# GasSensorCentral_v1_3.net
KiCad netlist of a schematic drawn in EAGLE
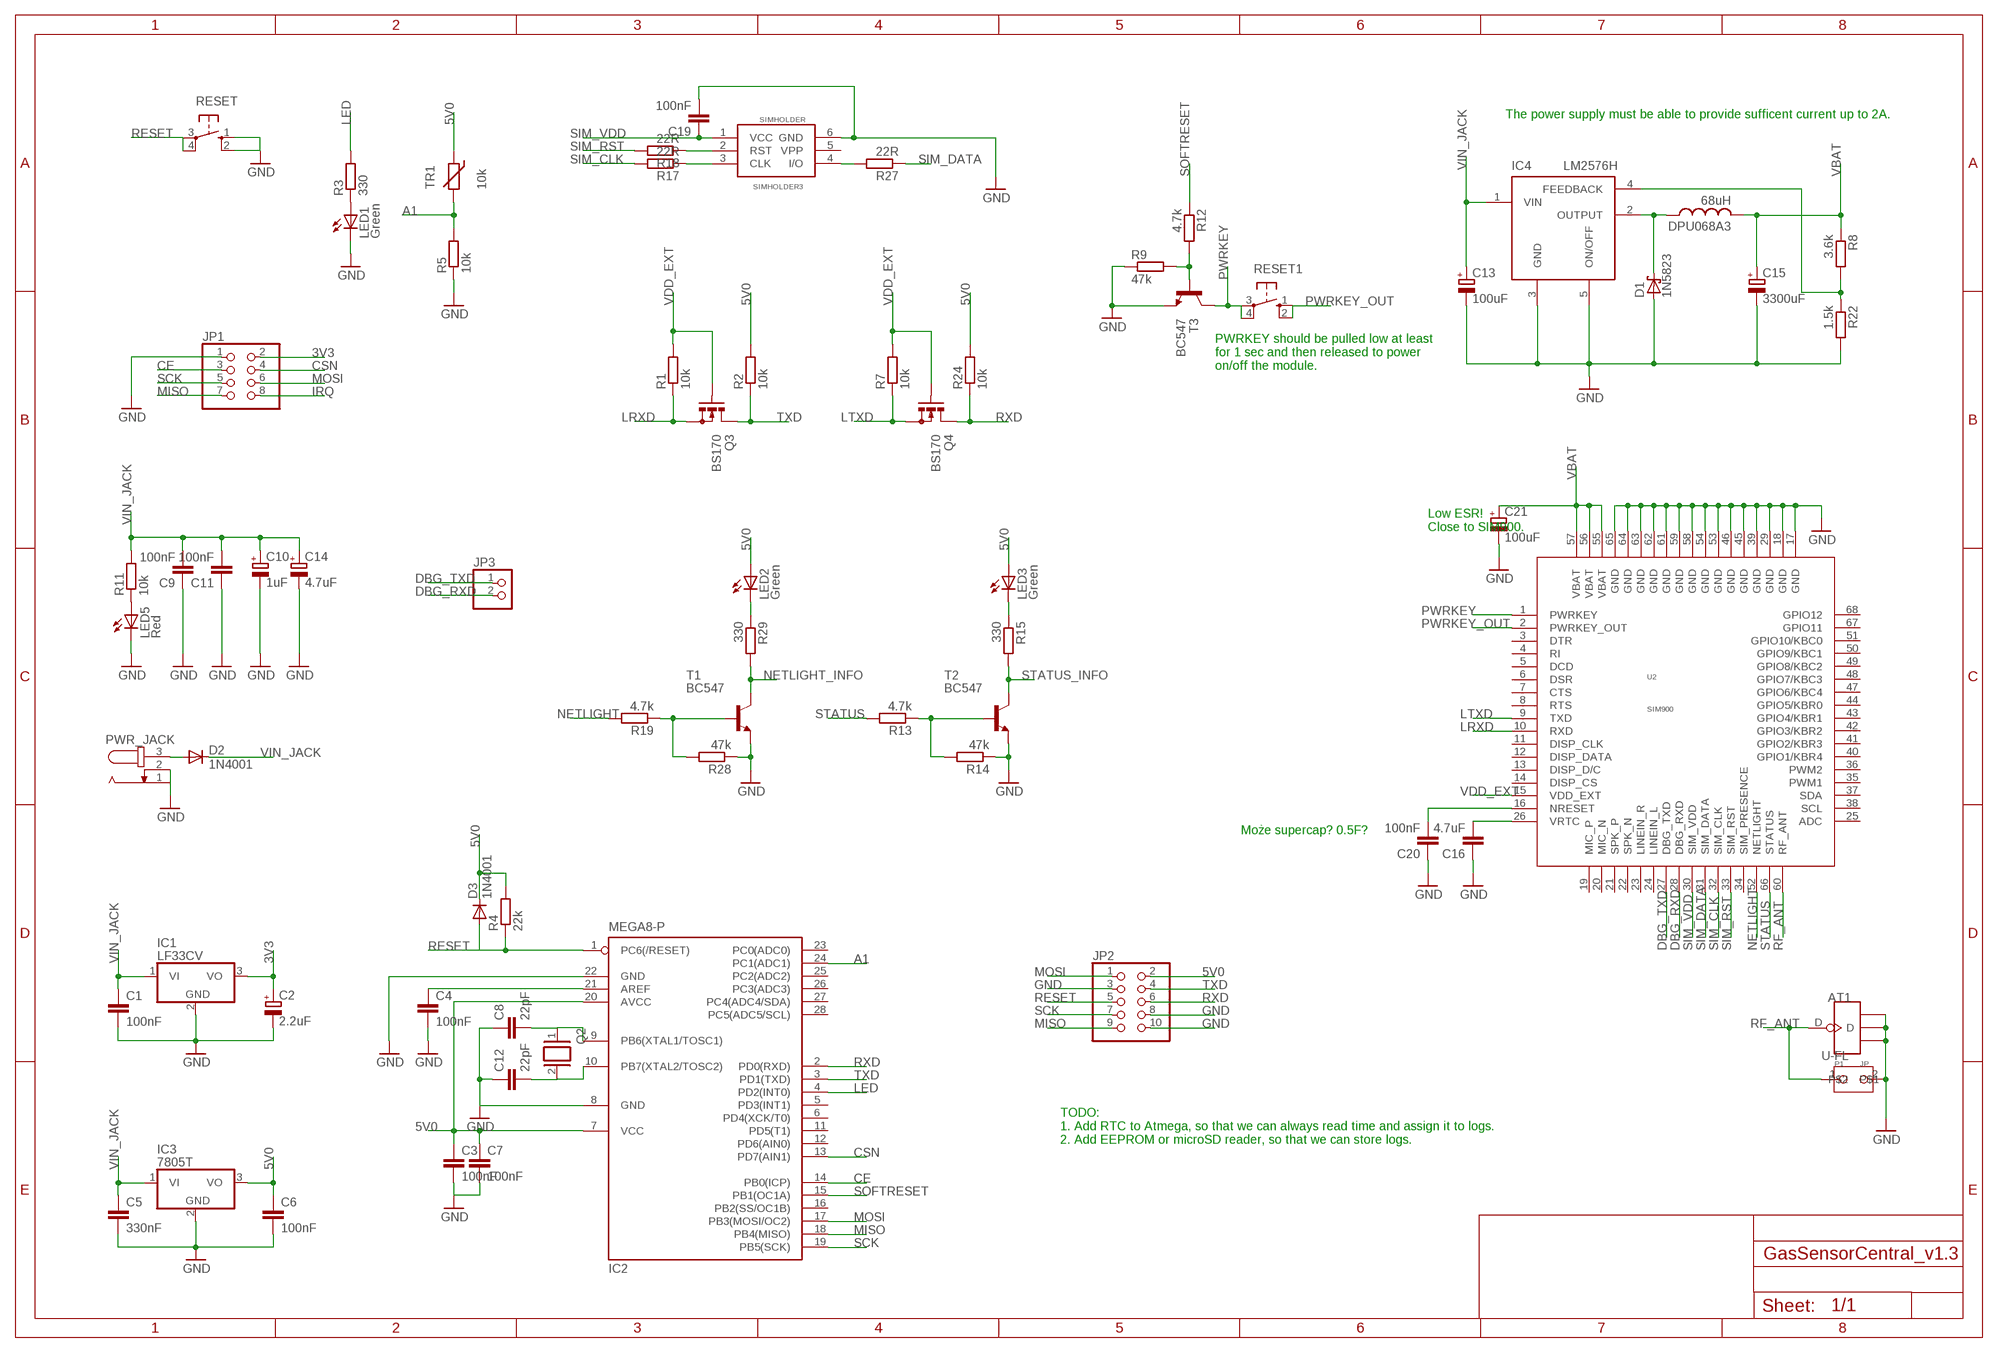
[diagram p0: schematic, sheet 1]

(export (version "E")
  (design (tool "Eeschema 10.0.6"))
  (components
    (comp (ref "AT1")
      (value "U-FL")
      (footprint "eagle-import:4P-U-FL")
      (libsource (lib "eagle-import") (part "ANTENNA-U-FL"))
    )
    (comp (ref "C1")
      (value "100nF")
      (footprint "eagle-import:C025-025X050")
      (libsource (lib "eagle-import") (part "C-EU025-025X050"))
    )
    (comp (ref "C2")
      (value "2.2uF")
      (footprint "eagle-import:E2,5-5")
      (libsource (lib "eagle-import") (part "CPOL-EUE2.5-5"))
    )
    (comp (ref "C3")
      (value "100nF")
      (footprint "eagle-import:C025-025X050")
      (libsource (lib "eagle-import") (part "C-EU025-025X050"))
    )
    (comp (ref "C4")
      (value "100nF")
      (footprint "eagle-import:C025-025X050")
      (libsource (lib "eagle-import") (part "C-EU025-025X050"))
    )
    (comp (ref "C5")
      (value "330nF")
      (footprint "eagle-import:C025-025X050")
      (libsource (lib "eagle-import") (part "C-EU025-025X050"))
    )
    (comp (ref "C6")
      (value "100nF")
      (footprint "eagle-import:C025-025X050")
      (libsource (lib "eagle-import") (part "C-EU025-025X050"))
    )
    (comp (ref "C7")
      (value "100nF")
      (footprint "eagle-import:C025-025X050")
      (libsource (lib "eagle-import") (part "C-EU025-025X050"))
    )
    (comp (ref "C8")
      (value "22pF")
      (footprint "eagle-import:C025-025X050")
      (libsource (lib "eagle-import") (part "C-EU025-025X050"))
    )
    (comp (ref "C9")
      (value "100nF")
      (footprint "eagle-import:C025-025X050")
      (libsource (lib "eagle-import") (part "C-EU025-025X050"))
    )
    (comp (ref "C10")
      (value "1uF")
      (footprint "eagle-import:E2,5-5")
      (libsource (lib "eagle-import") (part "CPOL-EUE2.5-5"))
    )
    (comp (ref "C11")
      (value "100nF")
      (footprint "eagle-import:C025-025X050")
      (libsource (lib "eagle-import") (part "C-EU025-025X050"))
    )
    (comp (ref "C12")
      (value "22pF")
      (footprint "eagle-import:C025-025X050")
      (libsource (lib "eagle-import") (part "C-EU025-025X050"))
    )
    (comp (ref "C13")
      (value "100uF")
      (footprint "eagle-import:E2,5-5")
      (libsource (lib "eagle-import") (part "CPOL-EUE2.5-5"))
    )
    (comp (ref "C14")
      (value "4.7uF")
      (footprint "eagle-import:E2,5-5")
      (libsource (lib "eagle-import") (part "CPOL-EUE2.5-5"))
    )
    (comp (ref "C15")
      (value "3300uF")
      (footprint "eagle-import:E3,5-10")
      (libsource (lib "eagle-import") (part "CPOL-EUE3.5-10"))
    )
    (comp (ref "C16")
      (value "4.7uF")
      (footprint "eagle-import:C025-025X050")
      (libsource (lib "eagle-import") (part "C-EU025-025X050"))
    )
    (comp (ref "C19")
      (value "100nF")
      (footprint "eagle-import:C025-025X050")
      (libsource (lib "eagle-import") (part "C-EU025-025X050"))
    )
    (comp (ref "C20")
      (value "100nF")
      (footprint "eagle-import:C025-025X050")
      (libsource (lib "eagle-import") (part "C-EU025-025X050"))
    )
    (comp (ref "C21")
      (value "100uF")
      (footprint "eagle-import:E2,5-5")
      (libsource (lib "eagle-import") (part "CPOL-EUE2.5-5"))
    )
    (comp (ref "D1")
      (value "1N5823")
      (footprint "eagle-import:DO41-7.6")
      (libsource (lib "eagle-import") (part "1N5817-B"))
    )
    (comp (ref "D2")
      (value "1N4001")
      (footprint "eagle-import:DO41-10")
      (libsource (lib "eagle-import") (part "1N4004"))
    )
    (comp (ref "D3")
      (value "1N4001")
      (footprint "eagle-import:DO41-10")
      (libsource (lib "eagle-import") (part "1N4004"))
    )
    (comp (ref "DPU068A3")
      (value "68uH")
      (footprint "eagle-import:TJ3-U1")
      (libsource (lib "eagle-import") (part "L-USTJ3-U1"))
    )
    (comp (ref "IC1")
      (value "LF33CV")
      (footprint "eagle-import:TO220H")
      (libsource (lib "eagle-import") (part "78T05"))
    )
    (comp (ref "IC2")
      (value "MEGA8-P")
      (footprint "eagle-import:DIL28-3")
      (libsource (lib "eagle-import") (part "MEGA8-P"))
    )
    (comp (ref "IC3")
      (value "7805T")
      (footprint "eagle-import:TO220H")
      (libsource (lib "eagle-import") (part "78T05"))
    )
    (comp (ref "IC4")
      (value "LM2576H")
      (footprint "eagle-import:TO220-52")
      (libsource (lib "eagle-import") (part "LM2576H"))
    )
    (comp (ref "JP1")
      (value "PINHD-2X4")
      (footprint "eagle-import:2X04")
      (libsource (lib "eagle-import") (part "PINHD-2X4"))
    )
    (comp (ref "JP2")
      (value "PINHD-2X5")
      (footprint "eagle-import:2X05")
      (libsource (lib "eagle-import") (part "PINHD-2X5"))
    )
    (comp (ref "JP3")
      (value "PINHD-1X2")
      (footprint "eagle-import:1X02")
      (libsource (lib "eagle-import") (part "PINHD-1X2"))
    )
    (comp (ref "LED1")
      (value "Green")
      (footprint "eagle-import:LED3MM")
      (libsource (lib "eagle-import") (part "LED3MM"))
    )
    (comp (ref "LED2")
      (value "Green")
      (footprint "eagle-import:LED3MM")
      (libsource (lib "eagle-import") (part "LED3MM"))
    )
    (comp (ref "LED3")
      (value "Green")
      (footprint "eagle-import:LED3MM")
      (libsource (lib "eagle-import") (part "LED3MM"))
    )
    (comp (ref "LED5")
      (value "Red")
      (footprint "eagle-import:LED3MM")
      (libsource (lib "eagle-import") (part "LED3MM"))
    )
    (comp (ref "P1") (value "JP") (footprint "eagle-import:JP") (libsource (lib "eagle-import") (part "JP")))
    (comp (ref "PWR_JACK")
      (value "JACK-PLUG0")
      (footprint "eagle-import:SPC4077")
      (libsource (lib "eagle-import") (part "JACK-PLUG0"))
    )
    (comp (ref "Q2")
      (value "XTAL/S")
      (footprint "eagle-import:QS")
      (libsource (lib "eagle-import") (part "XTAL/S"))
    )
    (comp (ref "Q3")
      (value "BS170")
      (footprint "eagle-import:SOT54E")
      (libsource (lib "eagle-import") (part "BS170"))
    )
    (comp (ref "Q4")
      (value "BS170")
      (footprint "eagle-import:SOT54E")
      (libsource (lib "eagle-import") (part "BS170"))
    )
    (comp (ref "R1")
      (value "10k")
      (footprint "eagle-import:0207_10")
      (libsource (lib "eagle-import") (part "R-EU_0207/10"))
    )
    (comp (ref "R2")
      (value "10k")
      (footprint "eagle-import:0207_10")
      (libsource (lib "eagle-import") (part "R-EU_0207/10"))
    )
    (comp (ref "R3")
      (value "330")
      (footprint "eagle-import:0207_10")
      (libsource (lib "eagle-import") (part "R-EU_0207/10"))
    )
    (comp (ref "R4")
      (value "22k")
      (footprint "eagle-import:0207_10")
      (libsource (lib "eagle-import") (part "R-EU_0207/10"))
    )
    (comp (ref "R5")
      (value "10k")
      (footprint "eagle-import:0207_10")
      (libsource (lib "eagle-import") (part "R-EU_0207/10"))
    )
    (comp (ref "R7")
      (value "10k")
      (footprint "eagle-import:0207_10")
      (libsource (lib "eagle-import") (part "R-EU_0207/10"))
    )
    (comp (ref "R8")
      (value "3.6k")
      (footprint "eagle-import:0207_10")
      (libsource (lib "eagle-import") (part "R-EU_0207/10"))
    )
    (comp (ref "R9")
      (value "47k")
      (footprint "eagle-import:0207_10")
      (libsource (lib "eagle-import") (part "R-EU_0207/10"))
    )
    (comp (ref "R11")
      (value "10k")
      (footprint "eagle-import:0207_10")
      (libsource (lib "eagle-import") (part "R-EU_0207/10"))
    )
    (comp (ref "R12")
      (value "4.7k")
      (footprint "eagle-import:0207_10")
      (libsource (lib "eagle-import") (part "R-EU_0207/10"))
    )
    (comp (ref "R13")
      (value "4.7k")
      (footprint "eagle-import:0207_10")
      (libsource (lib "eagle-import") (part "R-EU_0207/10"))
    )
    (comp (ref "R14")
      (value "47k")
      (footprint "eagle-import:0207_10")
      (libsource (lib "eagle-import") (part "R-EU_0207/10"))
    )
    (comp (ref "R15")
      (value "330")
      (footprint "eagle-import:0207_10")
      (libsource (lib "eagle-import") (part "R-EU_0207/10"))
    )
    (comp (ref "R17")
      (value "22R")
      (footprint "eagle-import:0207_10")
      (libsource (lib "eagle-import") (part "R-EU_0207/10"))
    )
    (comp (ref "R18")
      (value "22R")
      (footprint "eagle-import:0207_10")
      (libsource (lib "eagle-import") (part "R-EU_0207/10"))
    )
    (comp (ref "R19")
      (value "4.7k")
      (footprint "eagle-import:0207_10")
      (libsource (lib "eagle-import") (part "R-EU_0207/10"))
    )
    (comp (ref "R22")
      (value "1.5k")
      (footprint "eagle-import:0207_10")
      (libsource (lib "eagle-import") (part "R-EU_0207/10"))
    )
    (comp (ref "R24")
      (value "10k")
      (footprint "eagle-import:0207_10")
      (libsource (lib "eagle-import") (part "R-EU_0207/10"))
    )
    (comp (ref "R27")
      (value "22R")
      (footprint "eagle-import:0207_10")
      (libsource (lib "eagle-import") (part "R-EU_0207/10"))
    )
    (comp (ref "R28")
      (value "47k")
      (footprint "eagle-import:0207_10")
      (libsource (lib "eagle-import") (part "R-EU_0207/10"))
    )
    (comp (ref "R29")
      (value "330")
      (footprint "eagle-import:0207_10")
      (libsource (lib "eagle-import") (part "R-EU_0207/10"))
    )
    (comp (ref "RESET")
      (value "10-XX")
      (footprint "eagle-import:B3F-10XX")
      (fields (field (name "MPN") "B3F-1000"))
      (libsource (lib "eagle-import") (part "10-XX"))
    )
    (comp (ref "RESET1")
      (value "10-XX")
      (footprint "eagle-import:B3F-10XX")
      (fields (field (name "MPN") "B3F-1000"))
      (libsource (lib "eagle-import") (part "10-XX"))
    )
    (comp (ref "SIMHOLDER")
      (value "SIMHOLDER3")
      (footprint "eagle-import:SIMHOLDER3")
      (libsource (lib "eagle-import") (part "SIMHOLDER3"))
    )
    (comp (ref "T1")
      (value "BC547")
      (footprint "eagle-import:TO92")
      (libsource (lib "eagle-import") (part "BC547"))
    )
    (comp (ref "T2")
      (value "BC547")
      (footprint "eagle-import:TO92")
      (libsource (lib "eagle-import") (part "BC547"))
    )
    (comp (ref "T3")
      (value "BC547")
      (footprint "eagle-import:TO92")
      (libsource (lib "eagle-import") (part "BC547"))
    )
    (comp (ref "TR1")
      (value "10k")
      (footprint "eagle-import:RS-2,5")
      (libsource (lib "eagle-import") (part "THERMISTOR_R-2,5"))
    )
    (comp (ref "U2")
      (value "SIM900")
      (footprint "eagle-import:SIM900")
      (libsource (lib "eagle-import") (part "SIM900"))
    )
  )
  (nets
    (net (code "1") (name "/3V3") (class "Default")
      (node (ref "C2") (pin "+") (pinfunction "+_+") (pintype "passive"))
      (node (ref "IC1") (pin "3") (pinfunction "VO_3") (pintype "passive"))
      (node (ref "JP1") (pin "2") (pinfunction "2_2") (pintype "passive"))
    )
    (net (code "2") (name "/5V0") (class "Default")
      (node (ref "C3") (pin "1") (pinfunction "1_1") (pintype "passive"))
      (node (ref "C6") (pin "1") (pinfunction "1_1") (pintype "passive"))
      (node (ref "C7") (pin "1") (pinfunction "1_1") (pintype "passive"))
      (node (ref "D3") (pin "C") (pinfunction "C_C") (pintype "passive"))
      (node (ref "IC2") (pin "20") (pinfunction "AVCC_20") (pintype "power_in"))
      (node (ref "IC2") (pin "7") (pinfunction "VCC_7") (pintype "power_in"))
      (node (ref "IC3") (pin "3") (pinfunction "VO_3") (pintype "passive"))
      (node (ref "JP2") (pin "2") (pinfunction "2_2") (pintype "passive"))
      (node (ref "LED2") (pin "A") (pinfunction "A_A") (pintype "passive"))
      (node (ref "LED3") (pin "A") (pinfunction "A_A") (pintype "passive"))
      (node (ref "R2") (pin "2") (pinfunction "2_2") (pintype "passive"))
      (node (ref "R24") (pin "2") (pinfunction "2_2") (pintype "passive"))
      (node (ref "R4") (pin "2") (pinfunction "2_2") (pintype "passive"))
      (node (ref "TR1") (pin "1") (pinfunction "1_1") (pintype "passive"))
    )
    (net (code "3") (name "/A1") (class "Default")
      (node (ref "IC2") (pin "24") (pinfunction "PC1(ADC1)_24") (pintype "bidirectional"))
      (node (ref "R5") (pin "2") (pinfunction "2_2") (pintype "passive"))
      (node (ref "TR1") (pin "2") (pinfunction "2_2") (pintype "passive"))
    )
    (net (code "4") (name "/CE") (class "Default")
      (node (ref "IC2") (pin "14") (pinfunction "PB0(ICP)_14") (pintype "bidirectional"))
      (node (ref "JP1") (pin "3") (pinfunction "3_3") (pintype "passive"))
    )
    (net (code "5") (name "/CSN") (class "Default")
      (node (ref "IC2") (pin "13") (pinfunction "PD7(AIN1)_13") (pintype "bidirectional"))
      (node (ref "JP1") (pin "4") (pinfunction "4_4") (pintype "passive"))
    )
    (net (code "6") (name "/DBG_RXD") (class "Default")
      (node (ref "JP3") (pin "2") (pinfunction "2_2") (pintype "passive"))
      (node (ref "U2") (pin "28") (pinfunction "DBG_RXD_28") (pintype "input"))
    )
    (net (code "7") (name "/DBG_TXD") (class "Default")
      (node (ref "JP3") (pin "1") (pinfunction "1_1") (pintype "passive"))
      (node (ref "U2") (pin "27") (pinfunction "DBG_TXD_27") (pintype "output"))
    )
    (net (code "8") (name "/IRQ") (class "Default")
      (node (ref "JP1") (pin "8") (pinfunction "8_8") (pintype "passive"))
    )
    (net (code "9") (name "/LED") (class "Default")
      (node (ref "IC2") (pin "4") (pinfunction "PD2(INT0)_4") (pintype "bidirectional"))
      (node (ref "R3") (pin "2") (pinfunction "2_2") (pintype "passive"))
    )
    (net (code "10") (name "/LRXD") (class "Default")
      (node (ref "Q3") (pin "S") (pinfunction "S_S") (pintype "passive"))
      (node (ref "R1") (pin "1") (pinfunction "1_1") (pintype "passive"))
      (node (ref "U2") (pin "10") (pinfunction "RXD_10") (pintype "input"))
    )
    (net (code "11") (name "/LTXD") (class "Default")
      (node (ref "Q4") (pin "S") (pinfunction "S_S") (pintype "passive"))
      (node (ref "R7") (pin "1") (pinfunction "1_1") (pintype "passive"))
      (node (ref "U2") (pin "9") (pinfunction "TXD_9") (pintype "output"))
    )
    (net (code "12") (name "/MISO") (class "Default")
      (node (ref "IC2") (pin "18") (pinfunction "PB4(MISO)_18") (pintype "bidirectional"))
      (node (ref "JP1") (pin "7") (pinfunction "7_7") (pintype "passive"))
      (node (ref "JP2") (pin "9") (pinfunction "9_9") (pintype "passive"))
    )
    (net (code "13") (name "/MOSI") (class "Default")
      (node (ref "IC2") (pin "17") (pinfunction "PB3(MOSI/OC2)_17") (pintype "bidirectional"))
      (node (ref "JP1") (pin "6") (pinfunction "6_6") (pintype "passive"))
      (node (ref "JP2") (pin "1") (pinfunction "1_1") (pintype "passive"))
    )
    (net (code "14") (name "/NETLIGHT") (class "Default")
      (node (ref "R19") (pin "2") (pinfunction "2_2") (pintype "passive"))
      (node (ref "U2") (pin "52") (pinfunction "NETLIGHT_52") (pintype "output"))
    )
    (net (code "15") (name "/NETLIGHT_INFO") (class "Default")
      (node (ref "R29") (pin "2") (pinfunction "2_2") (pintype "passive"))
      (node (ref "T1") (pin "3") (pinfunction "C_3") (pintype "passive"))
    )
    (net (code "16") (name "/PWRKEY") (class "Default")
      (node (ref "RESET1") (pin "3") (pinfunction "P_3") (pintype "passive"))
      (node (ref "RESET1") (pin "4") (pinfunction "P1_4") (pintype "passive"))
      (node (ref "T3") (pin "3") (pinfunction "C_3") (pintype "passive"))
      (node (ref "U2") (pin "1") (pinfunction "PWRKEY_1") (pintype "input"))
    )
    (net (code "17") (name "/PWRKEY_OUT") (class "Default")
      (node (ref "RESET1") (pin "1") (pinfunction "S_1") (pintype "passive"))
      (node (ref "RESET1") (pin "2") (pinfunction "S1_2") (pintype "passive"))
      (node (ref "U2") (pin "2") (pinfunction "PWRKEY_OUT_2") (pintype "output"))
    )
    (net (code "18") (name "/RESET") (class "Default")
      (node (ref "D3") (pin "A") (pinfunction "A_A") (pintype "passive"))
      (node (ref "IC2") (pin "1") (pinfunction "PC6(/RESET)_1") (pintype "bidirectional"))
      (node (ref "JP2") (pin "5") (pinfunction "5_5") (pintype "passive"))
      (node (ref "R4") (pin "1") (pinfunction "1_1") (pintype "passive"))
      (node (ref "RESET") (pin "3") (pinfunction "P_3") (pintype "passive"))
      (node (ref "RESET") (pin "4") (pinfunction "P1_4") (pintype "passive"))
    )
    (net (code "19") (name "/RF_ANT") (class "Default")
      (node (ref "AT1") (pin "D") (pinfunction "D_D") (pintype "bidirectional"))
      (node (ref "P1") (pin "1") (pinfunction "P$1_1") (pintype "bidirectional"))
      (node (ref "U2") (pin "60") (pinfunction "RF_ANT_60") (pintype "bidirectional"))
    )
    (net (code "20") (name "/RXD") (class "Default")
      (node (ref "IC2") (pin "2") (pinfunction "PD0(RXD)_2") (pintype "bidirectional"))
      (node (ref "JP2") (pin "6") (pinfunction "6_6") (pintype "passive"))
      (node (ref "Q4") (pin "D") (pinfunction "D_D") (pintype "passive"))
      (node (ref "R24") (pin "1") (pinfunction "1_1") (pintype "passive"))
    )
    (net (code "21") (name "/SCK") (class "Default")
      (node (ref "IC2") (pin "19") (pinfunction "PB5(SCK)_19") (pintype "bidirectional"))
      (node (ref "JP1") (pin "5") (pinfunction "5_5") (pintype "passive"))
      (node (ref "JP2") (pin "7") (pinfunction "7_7") (pintype "passive"))
    )
    (net (code "22") (name "/SIM_CLK") (class "Default")
      (node (ref "R17") (pin "2") (pinfunction "2_2") (pintype "passive"))
      (node (ref "U2") (pin "32") (pinfunction "SIM_CLK_32") (pintype "output"))
    )
    (net (code "23") (name "/SIM_DATA") (class "Default")
      (node (ref "R27") (pin "1") (pinfunction "1_1") (pintype "passive"))
      (node (ref "U2") (pin "31") (pinfunction "SIM_DATA_31") (pintype "bidirectional"))
    )
    (net (code "24") (name "/SIM_RST") (class "Default")
      (node (ref "R18") (pin "2") (pinfunction "2_2") (pintype "passive"))
      (node (ref "U2") (pin "33") (pinfunction "SIM_RST_33") (pintype "output"))
    )
    (net (code "25") (name "/SIM_VDD") (class "Default")
      (node (ref "C19") (pin "1") (pinfunction "1_1") (pintype "passive"))
      (node (ref "SIMHOLDER") (pin "1") (pinfunction "VCC_1") (pintype "bidirectional"))
      (node (ref "U2") (pin "30") (pinfunction "SIM_VDD_30") (pintype "output"))
    )
    (net (code "26") (name "/SOFTRESET") (class "Default")
      (node (ref "IC2") (pin "15") (pinfunction "PB1(OC1A)_15") (pintype "bidirectional"))
      (node (ref "R12") (pin "1") (pinfunction "1_1") (pintype "passive"))
    )
    (net (code "27") (name "/STATUS") (class "Default")
      (node (ref "R13") (pin "2") (pinfunction "2_2") (pintype "passive"))
      (node (ref "U2") (pin "66") (pinfunction "STATUS_66") (pintype "output"))
    )
    (net (code "28") (name "/STATUS_INFO") (class "Default")
      (node (ref "R15") (pin "2") (pinfunction "2_2") (pintype "passive"))
      (node (ref "T2") (pin "3") (pinfunction "C_3") (pintype "passive"))
    )
    (net (code "29") (name "/TXD") (class "Default")
      (node (ref "IC2") (pin "3") (pinfunction "PD1(TXD)_3") (pintype "bidirectional"))
      (node (ref "JP2") (pin "4") (pinfunction "4_4") (pintype "passive"))
      (node (ref "Q3") (pin "D") (pinfunction "D_D") (pintype "passive"))
      (node (ref "R2") (pin "1") (pinfunction "1_1") (pintype "passive"))
    )
    (net (code "30") (name "/VBAT") (class "Default")
      (node (ref "C15") (pin "+") (pinfunction "+_+") (pintype "passive"))
      (node (ref "C21") (pin "+") (pinfunction "+_+") (pintype "passive"))
      (node (ref "DPU068A3") (pin "2") (pinfunction "2_2") (pintype "passive"))
      (node (ref "R8") (pin "1") (pinfunction "1_1") (pintype "passive"))
      (node (ref "U2") (pin "55") (pinfunction "VBAT_55") (pintype "power_in"))
      (node (ref "U2") (pin "56") (pinfunction "VBAT_56") (pintype "power_in"))
      (node (ref "U2") (pin "57") (pinfunction "VBAT_57") (pintype "power_in"))
    )
    (net (code "31") (name "/VDD_EXT") (class "Default")
      (node (ref "Q3") (pin "G") (pinfunction "G_G") (pintype "passive"))
      (node (ref "Q4") (pin "G") (pinfunction "G_G") (pintype "passive"))
      (node (ref "R1") (pin "2") (pinfunction "2_2") (pintype "passive"))
      (node (ref "R7") (pin "2") (pinfunction "2_2") (pintype "passive"))
      (node (ref "U2") (pin "15") (pinfunction "VDD_EXT_15") (pintype "output"))
    )
    (net (code "32") (name "/VIN_JACK") (class "Default")
      (node (ref "C1") (pin "1") (pinfunction "1_1") (pintype "passive"))
      (node (ref "C10") (pin "+") (pinfunction "+_+") (pintype "passive"))
      (node (ref "C11") (pin "2") (pinfunction "2_2") (pintype "passive"))
      (node (ref "C13") (pin "+") (pinfunction "+_+") (pintype "passive"))
      (node (ref "C14") (pin "+") (pinfunction "+_+") (pintype "passive"))
      (node (ref "C5") (pin "1") (pinfunction "1_1") (pintype "passive"))
      (node (ref "C9") (pin "2") (pinfunction "2_2") (pintype "passive"))
      (node (ref "D2") (pin "C") (pinfunction "C_C") (pintype "passive"))
      (node (ref "IC1") (pin "1") (pinfunction "VI_1") (pintype "input"))
      (node (ref "IC3") (pin "1") (pinfunction "VI_1") (pintype "input"))
      (node (ref "IC4") (pin "1") (pinfunction "VIN_1") (pintype "input"))
      (node (ref "R11") (pin "2") (pinfunction "2_2") (pintype "passive"))
    )
    (net (code "33") (name "GND") (class "Default")
      (node (ref "AT1") (pin "GND1") (pinfunction "GND1_GND1") (pintype "bidirectional"))
      (node (ref "AT1") (pin "GND2") (pinfunction "GND2_GND2") (pintype "bidirectional"))
      (node (ref "AT1") (pin "GND3") (pinfunction "GND3_GND3") (pintype "bidirectional"))
      (node (ref "C1") (pin "2") (pinfunction "2_2") (pintype "passive"))
      (node (ref "C10") (pin "-") (pinfunction "-_-") (pintype "passive"))
      (node (ref "C11") (pin "1") (pinfunction "1_1") (pintype "passive"))
      (node (ref "C12") (pin "1") (pinfunction "1_1") (pintype "passive"))
      (node (ref "C13") (pin "-") (pinfunction "-_-") (pintype "passive"))
      (node (ref "C14") (pin "-") (pinfunction "-_-") (pintype "passive"))
      (node (ref "C15") (pin "-") (pinfunction "-_-") (pintype "passive"))
      (node (ref "C16") (pin "1") (pinfunction "1_1") (pintype "passive"))
      (node (ref "C19") (pin "2") (pinfunction "2_2") (pintype "passive"))
      (node (ref "C2") (pin "-") (pinfunction "-_-") (pintype "passive"))
      (node (ref "C20") (pin "1") (pinfunction "1_1") (pintype "passive"))
      (node (ref "C21") (pin "-") (pinfunction "-_-") (pintype "passive"))
      (node (ref "C3") (pin "2") (pinfunction "2_2") (pintype "passive"))
      (node (ref "C4") (pin "2") (pinfunction "2_2") (pintype "passive"))
      (node (ref "C5") (pin "2") (pinfunction "2_2") (pintype "passive"))
      (node (ref "C6") (pin "2") (pinfunction "2_2") (pintype "passive"))
      (node (ref "C7") (pin "2") (pinfunction "2_2") (pintype "passive"))
      (node (ref "C8") (pin "1") (pinfunction "1_1") (pintype "passive"))
      (node (ref "C9") (pin "1") (pinfunction "1_1") (pintype "passive"))
      (node (ref "D1") (pin "A") (pinfunction "A_A") (pintype "passive"))
      (node (ref "IC1") (pin "2") (pinfunction "GND_2") (pintype "passive"))
      (node (ref "IC2") (pin "22") (pinfunction "GND_22") (pintype "power_in"))
      (node (ref "IC2") (pin "8") (pinfunction "GND_8") (pintype "power_in"))
      (node (ref "IC3") (pin "2") (pinfunction "GND_2") (pintype "passive"))
      (node (ref "IC4") (pin "3") (pinfunction "GND_3") (pintype "power_in"))
      (node (ref "IC4") (pin "5") (pinfunction "ON/OFF_5") (pintype "bidirectional"))
      (node (ref "JP1") (pin "1") (pinfunction "1_1") (pintype "passive"))
      (node (ref "JP2") (pin "10") (pinfunction "10_10") (pintype "passive"))
      (node (ref "JP2") (pin "3") (pinfunction "3_3") (pintype "passive"))
      (node (ref "JP2") (pin "8") (pinfunction "8_8") (pintype "passive"))
      (node (ref "LED1") (pin "K") (pinfunction "C_K") (pintype "passive"))
      (node (ref "LED5") (pin "K") (pinfunction "C_K") (pintype "passive"))
      (node (ref "P1") (pin "2") (pinfunction "P$2_2") (pintype "bidirectional"))
      (node (ref "PWR_JACK") (pin "1") (pinfunction "1_1") (pintype "passive"))
      (node (ref "PWR_JACK") (pin "2") (pinfunction "2_2") (pintype "passive"))
      (node (ref "R14") (pin "1") (pinfunction "1_1") (pintype "passive"))
      (node (ref "R22") (pin "2") (pinfunction "2_2") (pintype "passive"))
      (node (ref "R28") (pin "1") (pinfunction "1_1") (pintype "passive"))
      (node (ref "R5") (pin "1") (pinfunction "1_1") (pintype "passive"))
      (node (ref "R9") (pin "1") (pinfunction "1_1") (pintype "passive"))
      (node (ref "RESET") (pin "1") (pinfunction "S_1") (pintype "passive"))
      (node (ref "RESET") (pin "2") (pinfunction "S1_2") (pintype "passive"))
      (node (ref "SIMHOLDER") (pin "6") (pinfunction "GND_6") (pintype "bidirectional"))
      (node (ref "T1") (pin "1") (pinfunction "E_1") (pintype "passive"))
      (node (ref "T2") (pin "1") (pinfunction "E_1") (pintype "passive"))
      (node (ref "T3") (pin "1") (pinfunction "E_1") (pintype "passive"))
      (node (ref "U2") (pin "17") (pinfunction "GND_17") (pintype "power_in"))
      (node (ref "U2") (pin "18") (pinfunction "GND_18") (pintype "power_in"))
      (node (ref "U2") (pin "29") (pinfunction "GND_29") (pintype "power_in"))
      (node (ref "U2") (pin "39") (pinfunction "GND_39") (pintype "power_in"))
      (node (ref "U2") (pin "45") (pinfunction "GND_45") (pintype "power_in"))
      (node (ref "U2") (pin "46") (pinfunction "GND_46") (pintype "power_in"))
      (node (ref "U2") (pin "53") (pinfunction "GND_53") (pintype "power_in"))
      (node (ref "U2") (pin "54") (pinfunction "GND_54") (pintype "power_in"))
      (node (ref "U2") (pin "58") (pinfunction "GND_58") (pintype "power_in"))
      (node (ref "U2") (pin "59") (pinfunction "GND_59") (pintype "power_in"))
      (node (ref "U2") (pin "61") (pinfunction "GND_61") (pintype "power_in"))
      (node (ref "U2") (pin "62") (pinfunction "GND_62") (pintype "power_in"))
      (node (ref "U2") (pin "63") (pinfunction "GND_63") (pintype "power_in"))
      (node (ref "U2") (pin "64") (pinfunction "GND_64") (pintype "power_in"))
      (node (ref "U2") (pin "65") (pinfunction "GND_65") (pintype "power_in"))
    )
    (net (code "34") (name "Net-(D2-PadA)") (class "Default")
      (node (ref "D2") (pin "A") (pinfunction "A_A") (pintype "passive"))
      (node (ref "PWR_JACK") (pin "3") (pinfunction "3_3") (pintype "passive"))
    )
    (net (code "35") (name "Net-(IC2-AREF)") (class "Default")
      (node (ref "C4") (pin "1") (pinfunction "1_1") (pintype "passive"))
      (node (ref "IC2") (pin "21") (pinfunction "AREF_21") (pintype "passive"))
    )
    (net (code "36") (name "Net-(IC2-PB6(XTAL1{slash}TOSC1))") (class "Default")
      (node (ref "C8") (pin "2") (pinfunction "2_2") (pintype "passive"))
      (node (ref "IC2") (pin "9") (pinfunction "PB6(XTAL1/TOSC1)_9") (pintype "bidirectional"))
      (node (ref "Q2") (pin "1") (pinfunction "1_1") (pintype "passive"))
    )
    (net (code "37") (name "Net-(IC2-PB7(XTAL2{slash}TOSC2))") (class "Default")
      (node (ref "C12") (pin "2") (pinfunction "2_2") (pintype "passive"))
      (node (ref "IC2") (pin "10") (pinfunction "PB7(XTAL2/TOSC2)_10") (pintype "bidirectional"))
      (node (ref "Q2") (pin "2") (pinfunction "2_2") (pintype "passive"))
    )
    (net (code "38") (name "Net-(IC4-FEEDBACK)") (class "Default")
      (node (ref "IC4") (pin "4") (pinfunction "FEEDBACK_4") (pintype "bidirectional"))
      (node (ref "R22") (pin "1") (pinfunction "1_1") (pintype "passive"))
      (node (ref "R8") (pin "2") (pinfunction "2_2") (pintype "passive"))
    )
    (net (code "39") (name "Net-(IC4-OUTPUT)") (class "Default")
      (node (ref "D1") (pin "C") (pinfunction "C_C") (pintype "passive"))
      (node (ref "DPU068A3") (pin "1") (pinfunction "1_1") (pintype "passive"))
      (node (ref "IC4") (pin "2") (pinfunction "OUTPUT_2") (pintype "output"))
    )
    (net (code "40") (name "Net-(LED1-PadA)") (class "Default")
      (node (ref "LED1") (pin "A") (pinfunction "A_A") (pintype "passive"))
      (node (ref "R3") (pin "1") (pinfunction "1_1") (pintype "passive"))
    )
    (net (code "41") (name "Net-(LED2-C)") (class "Default")
      (node (ref "LED2") (pin "K") (pinfunction "C_K") (pintype "passive"))
      (node (ref "R29") (pin "1") (pinfunction "1_1") (pintype "passive"))
    )
    (net (code "42") (name "Net-(LED3-C)") (class "Default")
      (node (ref "LED3") (pin "K") (pinfunction "C_K") (pintype "passive"))
      (node (ref "R15") (pin "1") (pinfunction "1_1") (pintype "passive"))
    )
    (net (code "43") (name "Net-(LED5-PadA)") (class "Default")
      (node (ref "LED5") (pin "A") (pinfunction "A_A") (pintype "passive"))
      (node (ref "R11") (pin "1") (pinfunction "1_1") (pintype "passive"))
    )
    (net (code "44") (name "Net-(SIMHOLDER-CLK)") (class "Default")
      (node (ref "R17") (pin "1") (pinfunction "1_1") (pintype "passive"))
      (node (ref "SIMHOLDER") (pin "3") (pinfunction "CLK_3") (pintype "bidirectional"))
    )
    (net (code "45") (name "Net-(SIMHOLDER-I{slash}O)") (class "Default")
      (node (ref "R27") (pin "2") (pinfunction "2_2") (pintype "passive"))
      (node (ref "SIMHOLDER") (pin "4") (pinfunction "I/O_4") (pintype "bidirectional"))
    )
    (net (code "46") (name "Net-(SIMHOLDER-RST)") (class "Default")
      (node (ref "R18") (pin "1") (pinfunction "1_1") (pintype "passive"))
      (node (ref "SIMHOLDER") (pin "2") (pinfunction "RST_2") (pintype "bidirectional"))
    )
    (net (code "47") (name "Net-(T1-B)") (class "Default")
      (node (ref "R19") (pin "1") (pinfunction "1_1") (pintype "passive"))
      (node (ref "R28") (pin "2") (pinfunction "2_2") (pintype "passive"))
      (node (ref "T1") (pin "2") (pinfunction "B_2") (pintype "passive"))
    )
    (net (code "48") (name "Net-(T2-B)") (class "Default")
      (node (ref "R13") (pin "1") (pinfunction "1_1") (pintype "passive"))
      (node (ref "R14") (pin "2") (pinfunction "2_2") (pintype "passive"))
      (node (ref "T2") (pin "2") (pinfunction "B_2") (pintype "passive"))
    )
    (net (code "49") (name "Net-(T3-B)") (class "Default")
      (node (ref "R12") (pin "2") (pinfunction "2_2") (pintype "passive"))
      (node (ref "R9") (pin "2") (pinfunction "2_2") (pintype "passive"))
      (node (ref "T3") (pin "2") (pinfunction "B_2") (pintype "passive"))
    )
    (net (code "50") (name "Net-(U2-NRESET)") (class "Default")
      (node (ref "C20") (pin "2") (pinfunction "2_2") (pintype "passive"))
      (node (ref "U2") (pin "16") (pinfunction "NRESET_16") (pintype "input"))
    )
    (net (code "51") (name "Net-(U2-VRTC)") (class "Default")
      (node (ref "C16") (pin "2") (pinfunction "2_2") (pintype "passive"))
      (node (ref "U2") (pin "26") (pinfunction "VRTC_26") (pintype "bidirectional"))
    )
    (net (code "52") (name "unconnected-(IC2-PB2(SS{slash}OC1B)-Pad16)") (class "Default")
      (node (ref "IC2") (pin "16") (pinfunction "PB2(SS/OC1B)_16") (pintype "bidirectional"))
    )
    (net (code "53") (name "unconnected-(IC2-PC0(ADC0)-Pad23)") (class "Default")
      (node (ref "IC2") (pin "23") (pinfunction "PC0(ADC0)_23") (pintype "bidirectional"))
    )
    (net (code "54") (name "unconnected-(IC2-PC2(ADC2)-Pad25)") (class "Default")
      (node (ref "IC2") (pin "25") (pinfunction "PC2(ADC2)_25") (pintype "bidirectional"))
    )
    (net (code "55") (name "unconnected-(IC2-PC3(ADC3)-Pad26)") (class "Default")
      (node (ref "IC2") (pin "26") (pinfunction "PC3(ADC3)_26") (pintype "bidirectional"))
    )
    (net (code "56") (name "unconnected-(IC2-PC4(ADC4{slash}SDA)-Pad27)") (class "Default")
      (node (ref "IC2") (pin "27") (pinfunction "PC4(ADC4/SDA)_27") (pintype "bidirectional"))
    )
    (net (code "57") (name "unconnected-(IC2-PC5(ADC5{slash}SCL)-Pad28)") (class "Default")
      (node (ref "IC2") (pin "28") (pinfunction "PC5(ADC5/SCL)_28") (pintype "bidirectional"))
    )
    (net (code "58") (name "unconnected-(IC2-PD3(INT1)-Pad5)") (class "Default")
      (node (ref "IC2") (pin "5") (pinfunction "PD3(INT1)_5") (pintype "bidirectional"))
    )
    (net (code "59") (name "unconnected-(IC2-PD4(XCK{slash}T0)-Pad6)") (class "Default")
      (node (ref "IC2") (pin "6") (pinfunction "PD4(XCK/T0)_6") (pintype "bidirectional"))
    )
    (net (code "60") (name "unconnected-(IC2-PD5(T1)-Pad11)") (class "Default")
      (node (ref "IC2") (pin "11") (pinfunction "PD5(T1)_11") (pintype "bidirectional"))
    )
    (net (code "61") (name "unconnected-(IC2-PD6(AIN0)-Pad12)") (class "Default")
      (node (ref "IC2") (pin "12") (pinfunction "PD6(AIN0)_12") (pintype "bidirectional"))
    )
    (net (code "62") (name "unconnected-(SIMHOLDER-VPP-Pad5)") (class "Default")
      (node (ref "SIMHOLDER") (pin "5") (pinfunction "VPP_5") (pintype "bidirectional"))
    )
    (net (code "63") (name "unconnected-(U2-ADC-Pad25)") (class "Default")
      (node (ref "U2") (pin "25") (pinfunction "ADC_25") (pintype "input"))
    )
    (net (code "64") (name "unconnected-(U2-CTS-Pad7)") (class "Default")
      (node (ref "U2") (pin "7") (pinfunction "CTS_7") (pintype "output"))
    )
    (net (code "65") (name "unconnected-(U2-DCD-Pad5)") (class "Default")
      (node (ref "U2") (pin "5") (pinfunction "DCD_5") (pintype "output"))
    )
    (net (code "66") (name "unconnected-(U2-DISP_CLK-Pad11)") (class "Default")
      (node (ref "U2") (pin "11") (pinfunction "DISP_CLK_11") (pintype "output"))
    )
    (net (code "67") (name "unconnected-(U2-DISP_CS-Pad14)") (class "Default")
      (node (ref "U2") (pin "14") (pinfunction "DISP_CS_14") (pintype "output"))
    )
    (net (code "68") (name "unconnected-(U2-DISP_DATA-Pad12)") (class "Default")
      (node (ref "U2") (pin "12") (pinfunction "DISP_DATA_12") (pintype "bidirectional"))
    )
    (net (code "69") (name "unconnected-(U2-DISP_D{slash}C-Pad13)") (class "Default")
      (node (ref "U2") (pin "13") (pinfunction "DISP_D/C_13") (pintype "output"))
    )
    (net (code "70") (name "unconnected-(U2-DSR-Pad6)") (class "Default")
      (node (ref "U2") (pin "6") (pinfunction "DSR_6") (pintype "output"))
    )
    (net (code "71") (name "unconnected-(U2-DTR-Pad3)") (class "Default")
      (node (ref "U2") (pin "3") (pinfunction "DTR_3") (pintype "input"))
    )
    (net (code "72") (name "unconnected-(U2-GPIO1{slash}KBR4-Pad40)") (class "Default")
      (node (ref "U2") (pin "40") (pinfunction "GPIO1/KBR4_40") (pintype "output"))
    )
    (net (code "73") (name "unconnected-(U2-GPIO2{slash}KBR3-Pad41)") (class "Default")
      (node (ref "U2") (pin "41") (pinfunction "GPIO2/KBR3_41") (pintype "output"))
    )
    (net (code "74") (name "unconnected-(U2-GPIO3{slash}KBR2-Pad42)") (class "Default")
      (node (ref "U2") (pin "42") (pinfunction "GPIO3/KBR2_42") (pintype "output"))
    )
    (net (code "75") (name "unconnected-(U2-GPIO4{slash}KBR1-Pad43)") (class "Default")
      (node (ref "U2") (pin "43") (pinfunction "GPIO4/KBR1_43") (pintype "output"))
    )
    (net (code "76") (name "unconnected-(U2-GPIO5{slash}KBR0-Pad44)") (class "Default")
      (node (ref "U2") (pin "44") (pinfunction "GPIO5/KBR0_44") (pintype "output"))
    )
    (net (code "77") (name "unconnected-(U2-GPIO6{slash}KBC4-Pad47)") (class "Default")
      (node (ref "U2") (pin "47") (pinfunction "GPIO6/KBC4_47") (pintype "input"))
    )
    (net (code "78") (name "unconnected-(U2-GPIO7{slash}KBC3-Pad48)") (class "Default")
      (node (ref "U2") (pin "48") (pinfunction "GPIO7/KBC3_48") (pintype "bidirectional"))
    )
    (net (code "79") (name "unconnected-(U2-GPIO8{slash}KBC2-Pad49)") (class "Default")
      (node (ref "U2") (pin "49") (pinfunction "GPIO8/KBC2_49") (pintype "input"))
    )
    (net (code "80") (name "unconnected-(U2-GPIO9{slash}KBC1-Pad50)") (class "Default")
      (node (ref "U2") (pin "50") (pinfunction "GPIO9/KBC1_50") (pintype "input"))
    )
    (net (code "81") (name "unconnected-(U2-GPIO10{slash}KBC0-Pad51)") (class "Default")
      (node (ref "U2") (pin "51") (pinfunction "GPIO10/KBC0_51") (pintype "bidirectional"))
    )
    (net (code "82") (name "unconnected-(U2-GPIO11-Pad67)") (class "Default")
      (node (ref "U2") (pin "67") (pinfunction "GPIO11_67") (pintype "bidirectional"))
    )
    (net (code "83") (name "unconnected-(U2-GPIO12-Pad68)") (class "Default")
      (node (ref "U2") (pin "68") (pinfunction "GPIO12_68") (pintype "bidirectional"))
    )
    (net (code "84") (name "unconnected-(U2-LINEIN_L-Pad24)") (class "Default")
      (node (ref "U2") (pin "24") (pinfunction "LINEIN_L_24") (pintype "input"))
    )
    (net (code "85") (name "unconnected-(U2-LINEIN_R-Pad23)") (class "Default")
      (node (ref "U2") (pin "23") (pinfunction "LINEIN_R_23") (pintype "input"))
    )
    (net (code "86") (name "unconnected-(U2-MIC_N-Pad20)") (class "Default")
      (node (ref "U2") (pin "20") (pinfunction "MIC_N_20") (pintype "input"))
    )
    (net (code "87") (name "unconnected-(U2-MIC_P-Pad19)") (class "Default")
      (node (ref "U2") (pin "19") (pinfunction "MIC_P_19") (pintype "input"))
    )
    (net (code "88") (name "unconnected-(U2-PWM1-Pad35)") (class "Default")
      (node (ref "U2") (pin "35") (pinfunction "PWM1_35") (pintype "output"))
    )
    (net (code "89") (name "unconnected-(U2-PWM2-Pad36)") (class "Default")
      (node (ref "U2") (pin "36") (pinfunction "PWM2_36") (pintype "output"))
    )
    (net (code "90") (name "unconnected-(U2-RI-Pad4)") (class "Default")
      (node (ref "U2") (pin "4") (pinfunction "RI_4") (pintype "output"))
    )
    (net (code "91") (name "unconnected-(U2-RTS-Pad8)") (class "Default")
      (node (ref "U2") (pin "8") (pinfunction "RTS_8") (pintype "input"))
    )
    (net (code "92") (name "unconnected-(U2-SCL-Pad38)") (class "Default")
      (node (ref "U2") (pin "38") (pinfunction "SCL_38") (pintype "output"))
    )
    (net (code "93") (name "unconnected-(U2-SDA-Pad37)") (class "Default")
      (node (ref "U2") (pin "37") (pinfunction "SDA_37") (pintype "bidirectional"))
    )
    (net (code "94") (name "unconnected-(U2-SIM_PRESENCE-Pad34)") (class "Default")
      (node (ref "U2") (pin "34") (pinfunction "SIM_PRESENCE_34") (pintype "input"))
    )
    (net (code "95") (name "unconnected-(U2-SPK_N-Pad22)") (class "Default")
      (node (ref "U2") (pin "22") (pinfunction "SPK_N_22") (pintype "output"))
    )
    (net (code "96") (name "unconnected-(U2-SPK_P-Pad21)") (class "Default")
      (node (ref "U2") (pin "21") (pinfunction "SPK_P_21") (pintype "output"))
    )
  )
)
